# top_level.net
KiCad netlist of a schematic drawn in Altium Designer
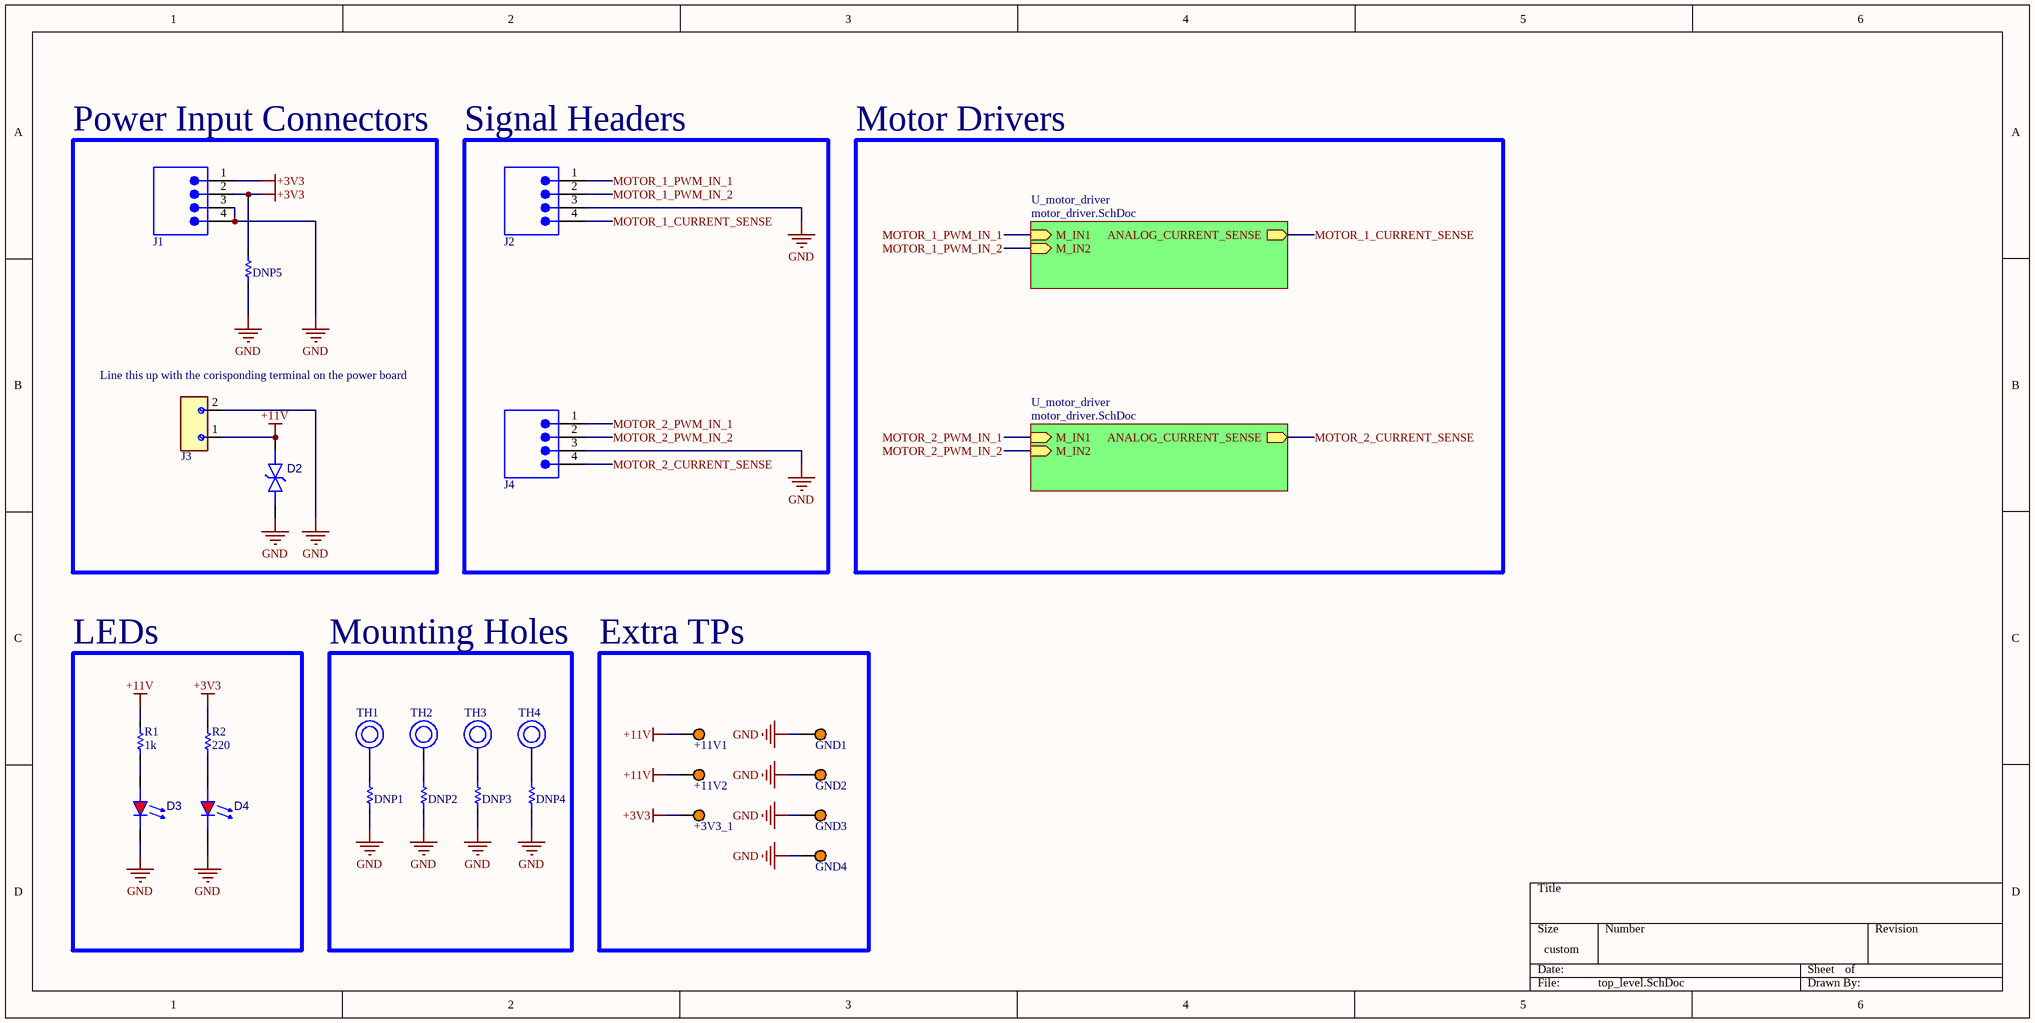
[diagram p0: top_level.SchDoc]

(export (version "E")
  (design (tool "Eeschema 10.0.6"))
  (components
    (comp (ref "+3V3_1")
      (value "TP - 5008 (Compact)")
      (footprint "5008 - Keystone Compact Footprint")
      (description "5008 - Orange PC Test Point, Compact Phosphor Bronze Silver Plating Through Hole Mounting Type")
      (libsource (lib "power_board_schhlib") (part "TP - 5008 (Compact)"))
    )
    (comp (ref "+11V1")
      (value "TP - 5008 (Compact)")
      (footprint "5008 - Keystone Compact Footprint")
      (description "5008 - Orange PC Test Point, Compact Phosphor Bronze Silver Plating Through Hole Mounting Type")
      (libsource (lib "power_board_schhlib") (part "TP - 5008 (Compact)"))
    )
    (comp (ref "+11V2")
      (value "TP - 5008 (Compact)")
      (footprint "5008 - Keystone Compact Footprint")
      (description "5008 - Orange PC Test Point, Compact Phosphor Bronze Silver Plating Through Hole Mounting Type")
      (libsource (lib "power_board_schhlib") (part "TP - 5008 (Compact)"))
    )
    (comp (ref "D2")
      (value "D - SMAJ15CA")
      (footprint "D - SMAJ15CA")
      (description "SMAJ15CA - 24.4V Clamp 16.4A Ipp Tvs Diode Surface Mount DO-214AC (SMA)")
      (libsource (lib "power_board_schhlib") (part "D - SMAJ15CA"))
    )
    (comp (ref "D3")
      (value "D - LTST-C193KRKT-5A")
      (footprint "LED 0603")
      (description "LTST-C193KRKT-5A - Red 631nm LED Indication - Discrete 2V 0603 (1608 Metric)")
      (libsource (lib "motor_board_schhlib") (part "D - LTST-C193KRKT-5A"))
    )
    (comp (ref "D4")
      (value "D - LTST-C193KRKT-5A")
      (footprint "LED 0603")
      (description "LTST-C193KRKT-5A - Red 631nm LED Indication - Discrete 2V 0603 (1608 Metric)")
      (libsource (lib "motor_board_schhlib") (part "D - LTST-C193KRKT-5A"))
    )
    (comp (ref "DNP1")
      (value "DNP - DNP PAD 0603")
      (footprint "DNP 0603")
      (libsource (lib "power_board_schhlib") (part "DNP - DNP PAD 0603"))
    )
    (comp (ref "DNP2")
      (value "DNP - DNP PAD 0603")
      (footprint "DNP 0603")
      (libsource (lib "power_board_schhlib") (part "DNP - DNP PAD 0603"))
    )
    (comp (ref "DNP3")
      (value "DNP - DNP PAD 0603")
      (footprint "DNP 0603")
      (libsource (lib "power_board_schhlib") (part "DNP - DNP PAD 0603"))
    )
    (comp (ref "DNP4")
      (value "DNP - DNP PAD 0603")
      (footprint "DNP 0603")
      (libsource (lib "power_board_schhlib") (part "DNP - DNP PAD 0603"))
    )
    (comp (ref "DNP5")
      (value "DNP - DNP PAD 0603")
      (footprint "DNP 0603")
      (libsource (lib "motor_board_schhlib") (part "DNP - DNP PAD 0603"))
    )
    (comp (ref "GND1")
      (value "TP - 5008 (Compact)")
      (footprint "5008 - Keystone Compact Footprint")
      (description "5008 - Orange PC Test Point, Compact Phosphor Bronze Silver Plating Through Hole Mounting Type")
      (libsource (lib "power_board_schhlib") (part "TP - 5008 (Compact)"))
    )
    (comp (ref "GND2")
      (value "TP - 5008 (Compact)")
      (footprint "5008 - Keystone Compact Footprint")
      (description "5008 - Orange PC Test Point, Compact Phosphor Bronze Silver Plating Through Hole Mounting Type")
      (libsource (lib "power_board_schhlib") (part "TP - 5008 (Compact)"))
    )
    (comp (ref "GND3")
      (value "TP - 5008 (Compact)")
      (footprint "5008 - Keystone Compact Footprint")
      (description "5008 - Orange PC Test Point, Compact Phosphor Bronze Silver Plating Through Hole Mounting Type")
      (libsource (lib "power_board_schhlib") (part "TP - 5008 (Compact)"))
    )
    (comp (ref "GND4")
      (value "TP - 5008 (Compact)")
      (footprint "5008 - Keystone Compact Footprint")
      (description "5008 - Orange PC Test Point, Compact Phosphor Bronze Silver Plating Through Hole Mounting Type")
      (libsource (lib "power_board_schhlib") (part "TP - 5008 (Compact)"))
    )
    (comp (ref "J1")
      (value "Copy of SMTC-TSW-106-07-X-D_1")
      (footprint "J - 61300411121")
      (description "61300411121 - Connector Header Through Hole 4 position 0.100\" (2.54mm)")
      (libsource (lib "motor_board_schhlib") (part "J - 61300411121"))
    )
    (comp (ref "J2")
      (value "Copy of SMTC-TSW-106-07-X-D_1")
      (footprint "J - 61300411121")
      (description "61300411121 - Connector Header Through Hole 4 position 0.100\" (2.54mm)")
      (libsource (lib "motor_board_schhlib") (part "J - 61300411121"))
    )
    (comp (ref "J3")
      (value "J - 691137710002")
      (footprint "J - 691137710002")
      (libsource (lib "power_board_schhlib") (part "J - 691137710002"))
    )
    (comp (ref "J4")
      (value "Copy of SMTC-TSW-106-07-X-D_1")
      (footprint "J - 61300411121")
      (description "61300411121 - Connector Header Through Hole 4 position 0.100\" (2.54mm)")
      (libsource (lib "motor_board_schhlib") (part "J - 61300411121"))
    )
    (comp (ref "R1")
      (value "1k")
      (footprint "RES 0603")
      (fields (field (name "Comment") "ERJ-PB3B1001V"))
      (libsource (lib "power_board_schhlib") (part "R - RES 1kR 0.2W 0.1% 0603"))
    )
    (comp (ref "R2")
      (value "220")
      (footprint "RES 0603")
      (fields (field (name "Comment") "R - RES 220R 0.33W 1% 0603"))
      (libsource (lib "power_board_schhlib") (part "R - RES 220R 0.33W 1% 0603"))
    )
    (comp (ref "TH1")
      (value "TH - M3 Mounting Hole")
      (footprint "M3 Mounting")
      (libsource (lib "power_board_schhlib") (part "TH - M3 Mounting Hole"))
    )
    (comp (ref "TH2")
      (value "TH - M3 Mounting Hole")
      (footprint "M3 Mounting")
      (libsource (lib "power_board_schhlib") (part "TH - M3 Mounting Hole"))
    )
    (comp (ref "TH3")
      (value "TH - M3 Mounting Hole")
      (footprint "M3 Mounting")
      (libsource (lib "power_board_schhlib") (part "TH - M3 Mounting Hole"))
    )
    (comp (ref "TH4")
      (value "TH - M3 Mounting Hole")
      (footprint "M3 Mounting")
      (libsource (lib "power_board_schhlib") (part "TH - M3 Mounting Hole"))
    )
  )
  (nets
    (net (code "1") (name "+3V3") (class "Default")
      (node (ref "+3V3_1") (pin "1") (pinfunction "1_1") (pintype "passive"))
      (node (ref "DNP5") (pin "2") (pinfunction "2_2") (pintype "passive"))
      (node (ref "J1") (pin "1") (pinfunction "1_1") (pintype "passive"))
      (node (ref "J1") (pin "2") (pinfunction "3_2") (pintype "passive"))
      (node (ref "R2") (pin "2") (pinfunction "2_2") (pintype "passive"))
    )
    (net (code "2") (name "+11V") (class "Default")
      (node (ref "+11V1") (pin "1") (pinfunction "1_1") (pintype "passive"))
      (node (ref "+11V2") (pin "1") (pinfunction "1_1") (pintype "passive"))
      (node (ref "D2") (pin "2") (pinfunction "A_2") (pintype "passive"))
      (node (ref "J3") (pin "1") (pinfunction "1_1") (pintype "passive"))
      (node (ref "R1") (pin "2") (pinfunction "2_2") (pintype "passive"))
    )
    (net (code "3") (name "/MOTOR_1_CURRENT_SENSE") (class "Default")
      (node (ref "J2") (pin "4") (pinfunction "7_4") (pintype "passive"))
    )
    (net (code "4") (name "/MOTOR_1_PWM_IN_1") (class "Default")
      (node (ref "J2") (pin "1") (pinfunction "1_1") (pintype "passive"))
    )
    (net (code "5") (name "/MOTOR_1_PWM_IN_2") (class "Default")
      (node (ref "J2") (pin "2") (pinfunction "3_2") (pintype "passive"))
    )
    (net (code "6") (name "/MOTOR_2_CURRENT_SENSE") (class "Default")
      (node (ref "J4") (pin "4") (pinfunction "7_4") (pintype "passive"))
    )
    (net (code "7") (name "/MOTOR_2_PWM_IN_1") (class "Default")
      (node (ref "J4") (pin "1") (pinfunction "1_1") (pintype "passive"))
    )
    (net (code "8") (name "/MOTOR_2_PWM_IN_2") (class "Default")
      (node (ref "J4") (pin "2") (pinfunction "3_2") (pintype "passive"))
    )
    (net (code "9") (name "GND") (class "Default")
      (node (ref "D2") (pin "1") (pinfunction "K_1") (pintype "passive"))
      (node (ref "D3") (pin "2") (pinfunction "K_2") (pintype "passive"))
      (node (ref "D4") (pin "2") (pinfunction "K_2") (pintype "passive"))
      (node (ref "DNP1") (pin "2") (pinfunction "2_2") (pintype "passive"))
      (node (ref "DNP2") (pin "2") (pinfunction "2_2") (pintype "passive"))
      (node (ref "DNP3") (pin "2") (pinfunction "2_2") (pintype "passive"))
      (node (ref "DNP4") (pin "2") (pinfunction "2_2") (pintype "passive"))
      (node (ref "DNP5") (pin "1") (pinfunction "1_1") (pintype "passive"))
      (node (ref "GND1") (pin "1") (pinfunction "1_1") (pintype "passive"))
      (node (ref "GND2") (pin "1") (pinfunction "1_1") (pintype "passive"))
      (node (ref "GND3") (pin "1") (pinfunction "1_1") (pintype "passive"))
      (node (ref "GND4") (pin "1") (pinfunction "1_1") (pintype "passive"))
      (node (ref "J1") (pin "3") (pinfunction "5_3") (pintype "passive"))
      (node (ref "J1") (pin "4") (pinfunction "7_4") (pintype "passive"))
      (node (ref "J2") (pin "3") (pinfunction "5_3") (pintype "passive"))
      (node (ref "J3") (pin "2") (pinfunction "2_2") (pintype "passive"))
      (node (ref "J4") (pin "3") (pinfunction "5_3") (pintype "passive"))
    )
    (net (code "10") (name "Net-(D3-A)") (class "Default")
      (node (ref "D3") (pin "1") (pinfunction "A_1") (pintype "passive"))
      (node (ref "R1") (pin "1") (pinfunction "1_1") (pintype "passive"))
    )
    (net (code "11") (name "Net-(D4-A)") (class "Default")
      (node (ref "D4") (pin "1") (pinfunction "A_1") (pintype "passive"))
      (node (ref "R2") (pin "1") (pinfunction "1_1") (pintype "passive"))
    )
    (net (code "12") (name "Net-(DNP1-Pad1)") (class "Default")
      (node (ref "DNP1") (pin "1") (pinfunction "1_1") (pintype "passive"))
      (node (ref "TH1") (pin "1") (pintype "passive"))
    )
    (net (code "13") (name "Net-(DNP2-Pad1)") (class "Default")
      (node (ref "DNP2") (pin "1") (pinfunction "1_1") (pintype "passive"))
      (node (ref "TH2") (pin "1") (pintype "passive"))
    )
    (net (code "14") (name "Net-(DNP3-Pad1)") (class "Default")
      (node (ref "DNP3") (pin "1") (pinfunction "1_1") (pintype "passive"))
      (node (ref "TH3") (pin "1") (pintype "passive"))
    )
    (net (code "15") (name "Net-(DNP4-Pad1)") (class "Default")
      (node (ref "DNP4") (pin "1") (pinfunction "1_1") (pintype "passive"))
      (node (ref "TH4") (pin "1") (pintype "passive"))
    )
  )
)
